# zerox_1_2.net
KiCad netlist of a schematic drawn in EAGLE
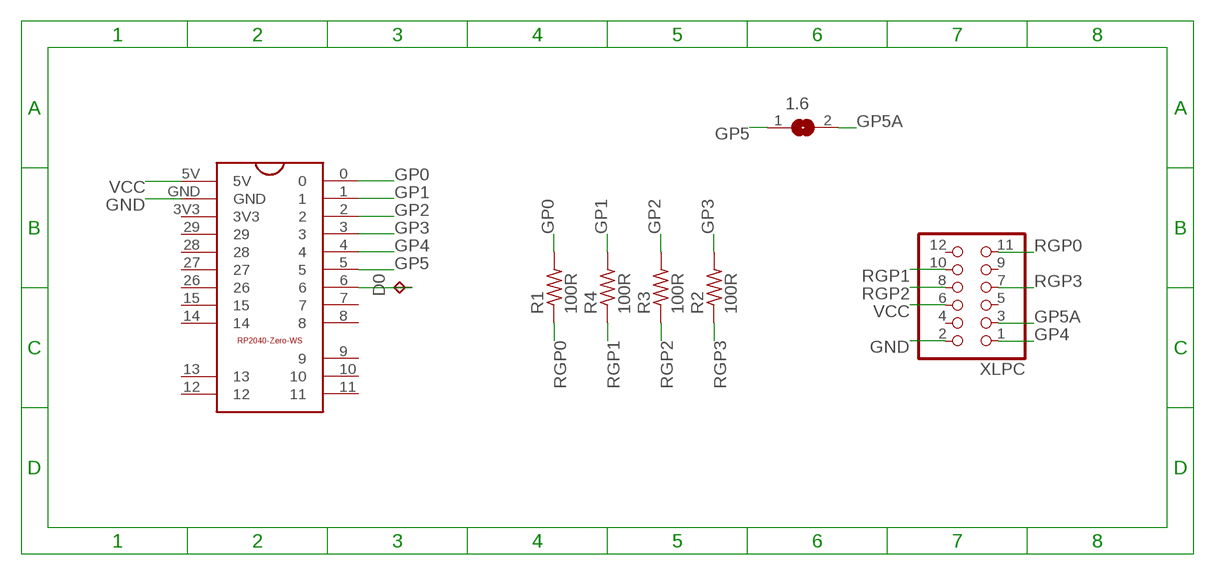
[diagram p0: schematic, sheet 1]

(export (version "E")
  (design (tool "Eeschema 10.0.6"))
  (components
    (comp (ref "1.6") (value "SJ") (footprint "eagle-import:SJ") (libsource (lib "eagle-import") (part "SJ")))
    (comp (ref "D0")
      (value "TPTP12SQ")
      (footprint "eagle-import:TP12SQ")
      (libsource (lib "eagle-import") (part "TPTP12SQ"))
    )
    (comp (ref "R1")
      (value "100R")
      (footprint "eagle-import:R0805")
      (libsource (lib "eagle-import") (part "R-US_R0805"))
    )
    (comp (ref "R2")
      (value "100R")
      (footprint "eagle-import:R0805")
      (libsource (lib "eagle-import") (part "R-US_R0805"))
    )
    (comp (ref "R3")
      (value "100R")
      (footprint "eagle-import:R0805")
      (libsource (lib "eagle-import") (part "R-US_R0805"))
    )
    (comp (ref "R4")
      (value "100R")
      (footprint "eagle-import:R0805")
      (libsource (lib "eagle-import") (part "R-US_R0805"))
    )
    (comp (ref "U$1")
      (value "RPI2040-WS-SMD")
      (footprint "eagle-import:RPI2040-WS")
      (libsource (lib "eagle-import") (part "RPI2040-WS-SMD"))
    )
    (comp (ref "XLPC")
      (value "PINHD-2X6")
      (footprint "eagle-import:2X06")
      (libsource (lib "eagle-import") (part "PINHD-2X6"))
    )
  )
  (nets
    (net (code "1") (name "/GND") (class "Default")
      (node (ref "U$1") (pin "GND") (pinfunction "GND_GND") (pintype "bidirectional"))
      (node (ref "XLPC") (pin "2") (pinfunction "2_2") (pintype "passive"))
    )
    (net (code "2") (name "/GP0") (class "Default")
      (node (ref "R1") (pin "2") (pinfunction "2_2") (pintype "passive"))
      (node (ref "U$1") (pin "0") (pinfunction "0_0") (pintype "bidirectional"))
    )
    (net (code "3") (name "/GP1") (class "Default")
      (node (ref "R4") (pin "2") (pinfunction "2_2") (pintype "passive"))
      (node (ref "U$1") (pin "1") (pinfunction "1_1") (pintype "bidirectional"))
    )
    (net (code "4") (name "/GP2") (class "Default")
      (node (ref "R3") (pin "2") (pinfunction "2_2") (pintype "passive"))
      (node (ref "U$1") (pin "2") (pinfunction "2_2") (pintype "bidirectional"))
    )
    (net (code "5") (name "/GP3") (class "Default")
      (node (ref "R2") (pin "2") (pinfunction "2_2") (pintype "passive"))
      (node (ref "U$1") (pin "3") (pinfunction "3_3") (pintype "bidirectional"))
    )
    (net (code "6") (name "/GP4") (class "Default")
      (node (ref "U$1") (pin "4") (pinfunction "4_4") (pintype "bidirectional"))
      (node (ref "XLPC") (pin "1") (pinfunction "1_1") (pintype "passive"))
    )
    (net (code "7") (name "/GP5") (class "Default")
      (node (ref "1.6") (pin "1") (pinfunction "1_1") (pintype "passive"))
      (node (ref "U$1") (pin "5") (pinfunction "5_5") (pintype "bidirectional"))
    )
    (net (code "8") (name "/GP5A") (class "Default")
      (node (ref "1.6") (pin "2") (pinfunction "2_2") (pintype "passive"))
      (node (ref "XLPC") (pin "3") (pinfunction "3_3") (pintype "passive"))
    )
    (net (code "9") (name "/RGP0") (class "Default")
      (node (ref "R1") (pin "1") (pinfunction "1_1") (pintype "passive"))
      (node (ref "XLPC") (pin "11") (pinfunction "11_11") (pintype "passive"))
    )
    (net (code "10") (name "/RGP1") (class "Default")
      (node (ref "R4") (pin "1") (pinfunction "1_1") (pintype "passive"))
      (node (ref "XLPC") (pin "10") (pinfunction "10_10") (pintype "passive"))
    )
    (net (code "11") (name "/RGP2") (class "Default")
      (node (ref "R3") (pin "1") (pinfunction "1_1") (pintype "passive"))
      (node (ref "XLPC") (pin "8") (pinfunction "8_8") (pintype "passive"))
    )
    (net (code "12") (name "/RGP3") (class "Default")
      (node (ref "R2") (pin "1") (pinfunction "1_1") (pintype "passive"))
      (node (ref "XLPC") (pin "7") (pinfunction "7_7") (pintype "passive"))
    )
    (net (code "13") (name "/VCC") (class "Default")
      (node (ref "U$1") (pin "5V") (pinfunction "5V_5V") (pintype "bidirectional"))
      (node (ref "XLPC") (pin "6") (pinfunction "6_6") (pintype "passive"))
    )
    (net (code "14") (name "Net-(D0-PadTP)") (class "Default")
      (node (ref "D0") (pin "TP") (pinfunction "TP_TP") (pintype "input"))
      (node (ref "U$1") (pin "6") (pinfunction "6_6") (pintype "bidirectional"))
    )
    (net (code "15") (name "unconnected-(U$1-Pad3V3)") (class "Default")
      (node (ref "U$1") (pin "3V3") (pinfunction "3V3_3V3") (pintype "bidirectional"))
    )
    (net (code "16") (name "unconnected-(U$1-Pad7)") (class "Default")
      (node (ref "U$1") (pin "7") (pinfunction "7_7") (pintype "bidirectional"))
    )
    (net (code "17") (name "unconnected-(U$1-Pad8)") (class "Default")
      (node (ref "U$1") (pin "8") (pinfunction "8_8") (pintype "bidirectional"))
    )
    (net (code "18") (name "unconnected-(U$1-Pad9)") (class "Default")
      (node (ref "U$1") (pin "9") (pinfunction "9_9") (pintype "bidirectional"))
    )
    (net (code "19") (name "unconnected-(U$1-Pad10)") (class "Default")
      (node (ref "U$1") (pin "10") (pinfunction "10_10") (pintype "bidirectional"))
    )
    (net (code "20") (name "unconnected-(U$1-Pad11)") (class "Default")
      (node (ref "U$1") (pin "11") (pinfunction "11_11") (pintype "bidirectional"))
    )
    (net (code "21") (name "unconnected-(U$1-Pad12)") (class "Default")
      (node (ref "U$1") (pin "12") (pinfunction "12_12") (pintype "bidirectional"))
    )
    (net (code "22") (name "unconnected-(U$1-Pad13)") (class "Default")
      (node (ref "U$1") (pin "13") (pinfunction "13_13") (pintype "bidirectional"))
    )
    (net (code "23") (name "unconnected-(U$1-Pad14)") (class "Default")
      (node (ref "U$1") (pin "14") (pinfunction "14_14") (pintype "bidirectional"))
    )
    (net (code "24") (name "unconnected-(U$1-Pad15)") (class "Default")
      (node (ref "U$1") (pin "15") (pinfunction "15_15") (pintype "bidirectional"))
    )
    (net (code "25") (name "unconnected-(U$1-Pad26)") (class "Default")
      (node (ref "U$1") (pin "26") (pinfunction "26_26") (pintype "bidirectional"))
    )
    (net (code "26") (name "unconnected-(U$1-Pad27)") (class "Default")
      (node (ref "U$1") (pin "27") (pinfunction "27_27") (pintype "bidirectional"))
    )
    (net (code "27") (name "unconnected-(U$1-Pad28)") (class "Default")
      (node (ref "U$1") (pin "28") (pinfunction "28_28") (pintype "bidirectional"))
    )
    (net (code "28") (name "unconnected-(U$1-Pad29)") (class "Default")
      (node (ref "U$1") (pin "29") (pinfunction "29_29") (pintype "bidirectional"))
    )
    (net (code "29") (name "unconnected-(XLPC-Pad4)") (class "Default")
      (node (ref "XLPC") (pin "4") (pinfunction "4_4") (pintype "passive"))
    )
    (net (code "30") (name "unconnected-(XLPC-Pad5)") (class "Default")
      (node (ref "XLPC") (pin "5") (pinfunction "5_5") (pintype "passive"))
    )
    (net (code "31") (name "unconnected-(XLPC-Pad9)") (class "Default")
      (node (ref "XLPC") (pin "9") (pinfunction "9_9") (pintype "passive"))
    )
    (net (code "32") (name "unconnected-(XLPC-Pad12)") (class "Default")
      (node (ref "XLPC") (pin "12") (pinfunction "12_12") (pintype "passive"))
    )
  )
)
